# tester-7410.net
KiCad netlist of a schematic drawn in EAGLE
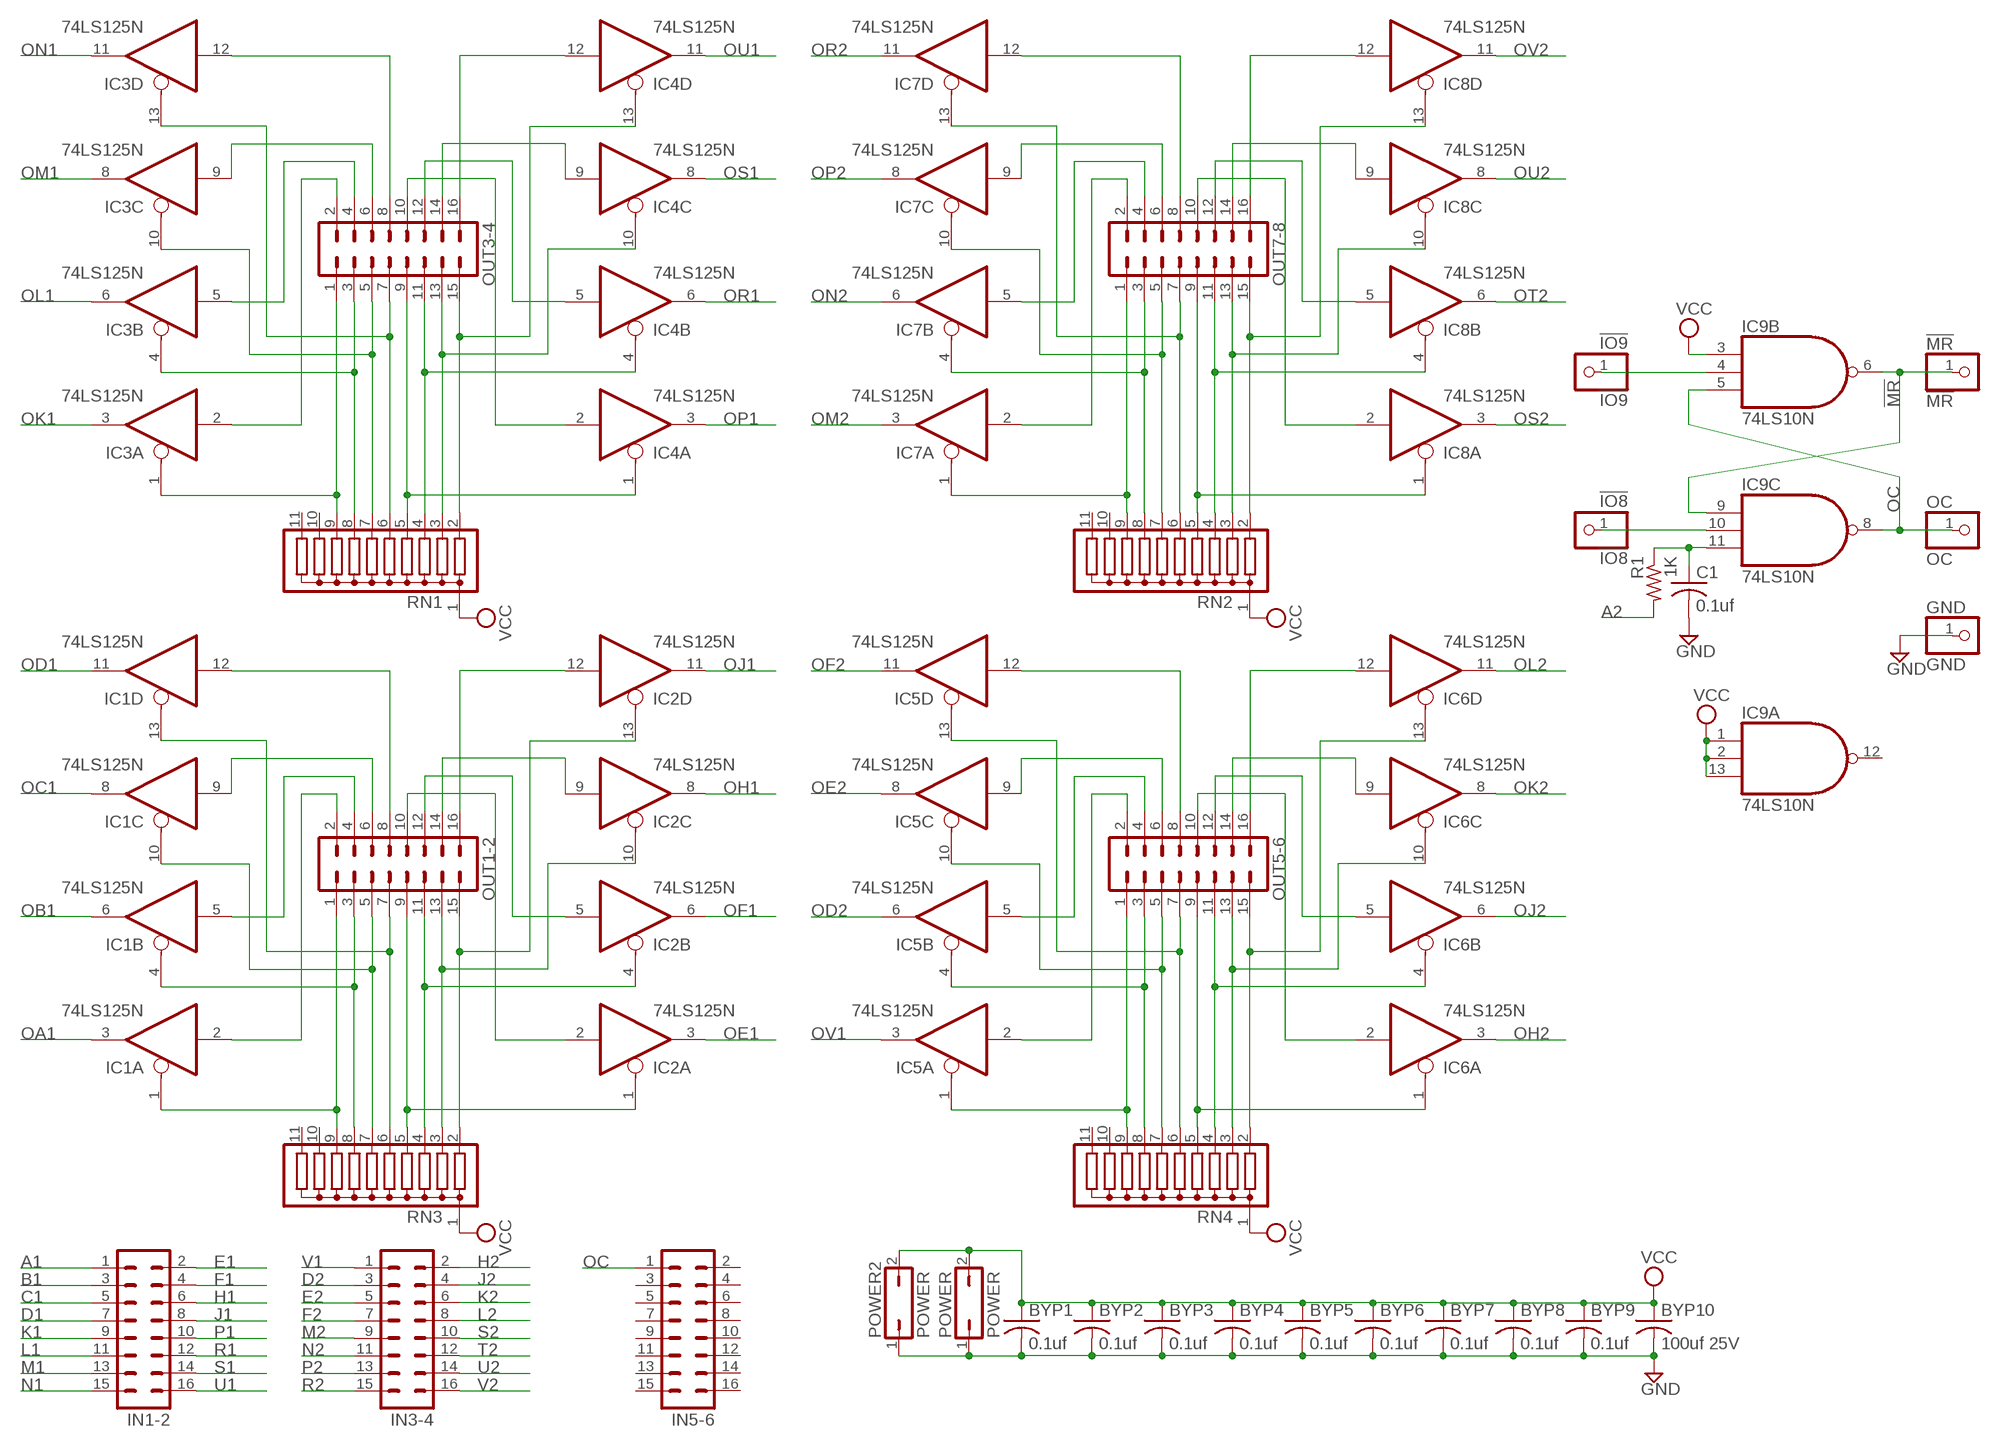
[diagram p0: schematic, sheet 1]
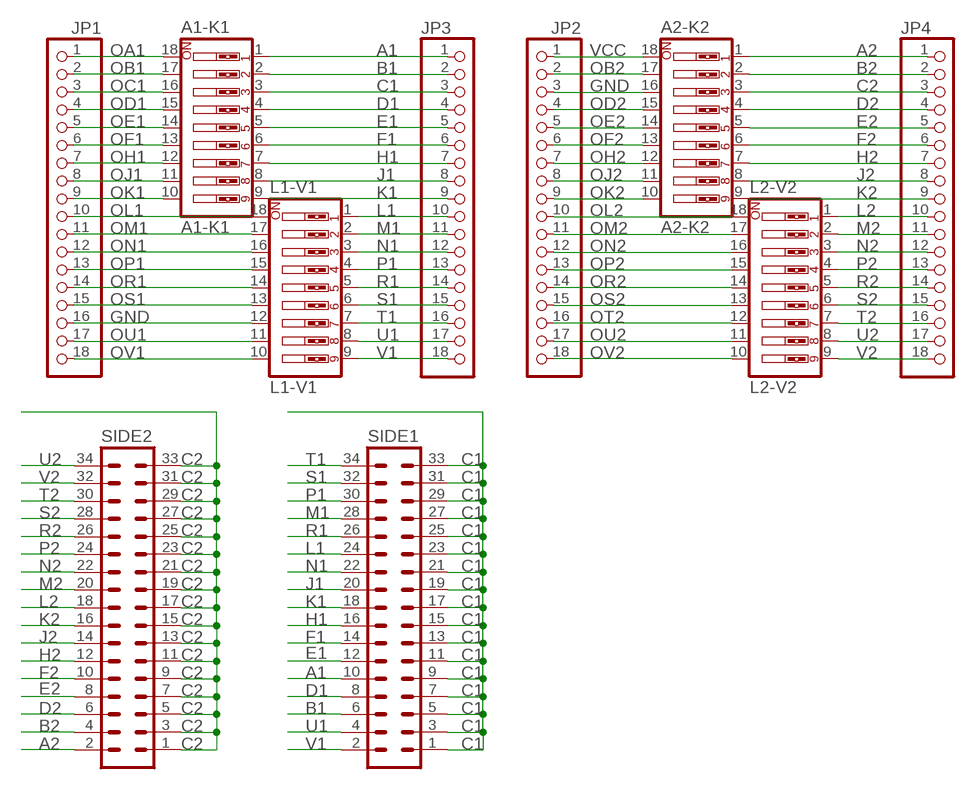
[diagram p1: schematic, sheet 2]

(export (version "E")
  (design (tool "Eeschema 10.0.6"))
  (components
    (comp (ref "!IO8")
      (value "!IO8")
      (footprint "eagle-import:1X01")
      (libsource (lib "eagle-import") (part "PINHD-1X1"))
    )
    (comp (ref "!IO9")
      (value "!IO9")
      (footprint "eagle-import:1X01")
      (libsource (lib "eagle-import") (part "PINHD-1X1"))
    )
    (comp (ref "!MR")
      (value "!MR")
      (footprint "eagle-import:1X01")
      (libsource (lib "eagle-import") (part "PINHD-1X1"))
    )
    (comp (ref "BYP1")
      (value "0.1uf")
      (footprint "eagle-import:C050-025X075")
      (libsource (lib "eagle-import") (part "C-US050-025X075"))
    )
    (comp (ref "BYP2")
      (value "0.1uf")
      (footprint "eagle-import:C050-025X075")
      (libsource (lib "eagle-import") (part "C-US050-025X075"))
    )
    (comp (ref "BYP3")
      (value "0.1uf")
      (footprint "eagle-import:C050-025X075")
      (libsource (lib "eagle-import") (part "C-US050-025X075"))
    )
    (comp (ref "BYP4")
      (value "0.1uf")
      (footprint "eagle-import:C050-025X075")
      (libsource (lib "eagle-import") (part "C-US050-025X075"))
    )
    (comp (ref "BYP5")
      (value "0.1uf")
      (footprint "eagle-import:C050-025X075")
      (libsource (lib "eagle-import") (part "C-US050-025X075"))
    )
    (comp (ref "BYP6")
      (value "0.1uf")
      (footprint "eagle-import:C050-025X075")
      (libsource (lib "eagle-import") (part "C-US050-025X075"))
    )
    (comp (ref "BYP7")
      (value "0.1uf")
      (footprint "eagle-import:C050-025X075")
      (libsource (lib "eagle-import") (part "C-US050-025X075"))
    )
    (comp (ref "BYP8")
      (value "0.1uf")
      (footprint "eagle-import:C050-025X075")
      (libsource (lib "eagle-import") (part "C-US050-025X075"))
    )
    (comp (ref "BYP9")
      (value "0.1uf")
      (footprint "eagle-import:C050-025X075")
      (libsource (lib "eagle-import") (part "C-US050-025X075"))
    )
    (comp (ref "BYP10")
      (value "100uf 25V")
      (footprint "eagle-import:C150-064X183")
      (libsource (lib "eagle-import") (part "C-US150-064X183"))
    )
    (comp (ref "C1")
      (value "0.1uf")
      (footprint "eagle-import:C050-025X075")
      (libsource (lib "eagle-import") (part "C-US050-025X075"))
    )
    (comp (ref "GND")
      (value "GND")
      (footprint "eagle-import:1X01")
      (libsource (lib "eagle-import") (part "PINHD-1X1"))
    )
    (comp (ref "IC1")
      (value "74LS125N")
      (footprint "eagle-import:DIL14")
      (libsource (lib "eagle-import") (part "74125NLS"))
    )
    (comp (ref "IC2")
      (value "74LS125N")
      (footprint "eagle-import:DIL14")
      (libsource (lib "eagle-import") (part "74125NLS"))
    )
    (comp (ref "IC3")
      (value "74LS125N")
      (footprint "eagle-import:DIL14")
      (libsource (lib "eagle-import") (part "74125NLS"))
    )
    (comp (ref "IC4")
      (value "74LS125N")
      (footprint "eagle-import:DIL14")
      (libsource (lib "eagle-import") (part "74125NLS"))
    )
    (comp (ref "IC5")
      (value "74LS125N")
      (footprint "eagle-import:DIL14")
      (libsource (lib "eagle-import") (part "74125NLS"))
    )
    (comp (ref "IC6")
      (value "74LS125N")
      (footprint "eagle-import:DIL14")
      (libsource (lib "eagle-import") (part "74125NLS"))
    )
    (comp (ref "IC7")
      (value "74LS125N")
      (footprint "eagle-import:DIL14")
      (libsource (lib "eagle-import") (part "74125NLS"))
    )
    (comp (ref "IC8")
      (value "74LS125N")
      (footprint "eagle-import:DIL14")
      (libsource (lib "eagle-import") (part "74125NLS"))
    )
    (comp (ref "IC9")
      (value "74LS10N")
      (footprint "eagle-import:DIL14")
      (libsource (lib "eagle-import") (part "7410NLS"))
    )
    (comp (ref "IN1-2")
      (value "MA08-2")
      (footprint "eagle-import:MA08-2")
      (libsource (lib "eagle-import") (part "MA08-2"))
    )
    (comp (ref "IN3-4")
      (value "MA08-2")
      (footprint "eagle-import:MA08-2")
      (libsource (lib "eagle-import") (part "MA08-2"))
    )
    (comp (ref "IN5-6")
      (value "MA08-2")
      (footprint "eagle-import:MA08-2")
      (libsource (lib "eagle-import") (part "MA08-2"))
    )
    (comp (ref "OC")
      (value "OC")
      (footprint "eagle-import:1X01")
      (libsource (lib "eagle-import") (part "PINHD-1X1"))
    )
    (comp (ref "OUT1-2")
      (value "MA08-2")
      (footprint "eagle-import:MA08-2")
      (libsource (lib "eagle-import") (part "MA08-2"))
    )
    (comp (ref "OUT3-4")
      (value "MA08-2")
      (footprint "eagle-import:MA08-2")
      (libsource (lib "eagle-import") (part "MA08-2"))
    )
    (comp (ref "OUT5-6")
      (value "MA08-2")
      (footprint "eagle-import:MA08-2")
      (libsource (lib "eagle-import") (part "MA08-2"))
    )
    (comp (ref "OUT7-8")
      (value "MA08-2")
      (footprint "eagle-import:MA08-2")
      (libsource (lib "eagle-import") (part "MA08-2"))
    )
    (comp (ref "POWER")
      (value "POWER")
      (footprint "eagle-import:JP1")
      (libsource (lib "eagle-import") (part "JP1Q"))
    )
    (comp (ref "POWER2")
      (value "POWER")
      (footprint "eagle-import:JP1")
      (libsource (lib "eagle-import") (part "JP1Q"))
    )
    (comp (ref "R1")
      (value "1K")
      (footprint "eagle-import:0207_10")
      (libsource (lib "eagle-import") (part "R-US_0207/10"))
    )
    (comp (ref "RN1")
      (value "G10R")
      (footprint "eagle-import:SIL11")
      (libsource (lib "eagle-import") (part "G10R"))
    )
    (comp (ref "RN2")
      (value "G10R")
      (footprint "eagle-import:SIL11")
      (libsource (lib "eagle-import") (part "G10R"))
    )
    (comp (ref "RN3")
      (value "G10R")
      (footprint "eagle-import:SIL11")
      (libsource (lib "eagle-import") (part "G10R"))
    )
    (comp (ref "RN4")
      (value "G10R")
      (footprint "eagle-import:SIL11")
      (libsource (lib "eagle-import") (part "G10R"))
    )
    (comp (ref "A1-K1")
      (value "A1-K1")
      (footprint "eagle-import:EDG-09")
      (libsource (lib "eagle-import") (part "SW_DIP-9"))
    )
    (comp (ref "A2-K2")
      (value "A2-K2")
      (footprint "eagle-import:EDG-09")
      (libsource (lib "eagle-import") (part "SW_DIP-9"))
    )
    (comp (ref "JP1")
      (value "PINHD-1X18")
      (footprint "eagle-import:1X18")
      (libsource (lib "eagle-import") (part "PINHD-1X18"))
    )
    (comp (ref "JP2")
      (value "PINHD-1X18")
      (footprint "eagle-import:1X18")
      (libsource (lib "eagle-import") (part "PINHD-1X18"))
    )
    (comp (ref "JP3")
      (value "PINHD-1X18")
      (footprint "eagle-import:1X18")
      (libsource (lib "eagle-import") (part "PINHD-1X18"))
    )
    (comp (ref "JP4")
      (value "PINHD-1X18")
      (footprint "eagle-import:1X18")
      (libsource (lib "eagle-import") (part "PINHD-1X18"))
    )
    (comp (ref "L1-V1")
      (value "L1-V1")
      (footprint "eagle-import:EDG-09")
      (libsource (lib "eagle-import") (part "SW_DIP-9"))
    )
    (comp (ref "L2-V2")
      (value "L2-V2")
      (footprint "eagle-import:EDG-09")
      (libsource (lib "eagle-import") (part "SW_DIP-9"))
    )
    (comp (ref "SIDE1")
      (value "MA17-2")
      (footprint "eagle-import:MA17-2")
      (libsource (lib "eagle-import") (part "MA17-2"))
    )
    (comp (ref "SIDE2")
      (value "MA17-2")
      (footprint "eagle-import:MA17-2")
      (libsource (lib "eagle-import") (part "MA17-2"))
    )
  )
  (nets
    (net (code "1") (name "A1") (class "Default")
      (node (ref "A1-K1") (pin "1") (pinfunction "1_1") (pintype "passive"))
      (node (ref "IN1-2") (pin "1") (pinfunction "1_1") (pintype "passive"))
      (node (ref "JP3") (pin "1") (pinfunction "1_1") (pintype "passive"))
      (node (ref "SIDE1") (pin "10") (pinfunction "10_10") (pintype "passive"))
    )
    (net (code "2") (name "A2") (class "Default")
      (node (ref "A2-K2") (pin "1") (pinfunction "1_1") (pintype "passive"))
      (node (ref "JP4") (pin "1") (pinfunction "1_1") (pintype "passive"))
      (node (ref "R1") (pin "2") (pinfunction "2_2") (pintype "passive"))
      (node (ref "SIDE2") (pin "2") (pinfunction "2_2") (pintype "passive"))
    )
    (net (code "3") (name "B1") (class "Default")
      (node (ref "A1-K1") (pin "2") (pinfunction "2_2") (pintype "passive"))
      (node (ref "IN1-2") (pin "3") (pinfunction "3_3") (pintype "passive"))
      (node (ref "JP3") (pin "2") (pinfunction "2_2") (pintype "passive"))
      (node (ref "SIDE1") (pin "6") (pinfunction "6_6") (pintype "passive"))
    )
    (net (code "4") (name "B2") (class "Default")
      (node (ref "A2-K2") (pin "2") (pinfunction "2_2") (pintype "passive"))
      (node (ref "JP4") (pin "2") (pinfunction "2_2") (pintype "passive"))
      (node (ref "SIDE2") (pin "4") (pinfunction "4_4") (pintype "passive"))
    )
    (net (code "5") (name "C1") (class "Default")
      (node (ref "A1-K1") (pin "3") (pinfunction "3_3") (pintype "passive"))
      (node (ref "IN1-2") (pin "5") (pinfunction "5_5") (pintype "passive"))
      (node (ref "JP3") (pin "3") (pinfunction "3_3") (pintype "passive"))
      (node (ref "SIDE1") (pin "1") (pinfunction "1_1") (pintype "passive"))
      (node (ref "SIDE1") (pin "11") (pinfunction "11_11") (pintype "passive"))
      (node (ref "SIDE1") (pin "13") (pinfunction "13_13") (pintype "passive"))
      (node (ref "SIDE1") (pin "15") (pinfunction "15_15") (pintype "passive"))
      (node (ref "SIDE1") (pin "17") (pinfunction "17_17") (pintype "passive"))
      (node (ref "SIDE1") (pin "19") (pinfunction "19_19") (pintype "passive"))
      (node (ref "SIDE1") (pin "21") (pinfunction "21_21") (pintype "passive"))
      (node (ref "SIDE1") (pin "23") (pinfunction "23_23") (pintype "passive"))
      (node (ref "SIDE1") (pin "25") (pinfunction "25_25") (pintype "passive"))
      (node (ref "SIDE1") (pin "27") (pinfunction "27_27") (pintype "passive"))
      (node (ref "SIDE1") (pin "29") (pinfunction "29_29") (pintype "passive"))
      (node (ref "SIDE1") (pin "3") (pinfunction "3_3") (pintype "passive"))
      (node (ref "SIDE1") (pin "31") (pinfunction "31_31") (pintype "passive"))
      (node (ref "SIDE1") (pin "33") (pinfunction "33_33") (pintype "passive"))
      (node (ref "SIDE1") (pin "5") (pinfunction "5_5") (pintype "passive"))
      (node (ref "SIDE1") (pin "7") (pinfunction "7_7") (pintype "passive"))
      (node (ref "SIDE1") (pin "9") (pinfunction "9_9") (pintype "passive"))
    )
    (net (code "6") (name "C2") (class "Default")
      (node (ref "A2-K2") (pin "3") (pinfunction "3_3") (pintype "passive"))
      (node (ref "JP4") (pin "3") (pinfunction "3_3") (pintype "passive"))
      (node (ref "SIDE2") (pin "1") (pinfunction "1_1") (pintype "passive"))
      (node (ref "SIDE2") (pin "11") (pinfunction "11_11") (pintype "passive"))
      (node (ref "SIDE2") (pin "13") (pinfunction "13_13") (pintype "passive"))
      (node (ref "SIDE2") (pin "15") (pinfunction "15_15") (pintype "passive"))
      (node (ref "SIDE2") (pin "17") (pinfunction "17_17") (pintype "passive"))
      (node (ref "SIDE2") (pin "19") (pinfunction "19_19") (pintype "passive"))
      (node (ref "SIDE2") (pin "21") (pinfunction "21_21") (pintype "passive"))
      (node (ref "SIDE2") (pin "23") (pinfunction "23_23") (pintype "passive"))
      (node (ref "SIDE2") (pin "25") (pinfunction "25_25") (pintype "passive"))
      (node (ref "SIDE2") (pin "27") (pinfunction "27_27") (pintype "passive"))
      (node (ref "SIDE2") (pin "29") (pinfunction "29_29") (pintype "passive"))
      (node (ref "SIDE2") (pin "3") (pinfunction "3_3") (pintype "passive"))
      (node (ref "SIDE2") (pin "31") (pinfunction "31_31") (pintype "passive"))
      (node (ref "SIDE2") (pin "33") (pinfunction "33_33") (pintype "passive"))
      (node (ref "SIDE2") (pin "5") (pinfunction "5_5") (pintype "passive"))
      (node (ref "SIDE2") (pin "7") (pinfunction "7_7") (pintype "passive"))
      (node (ref "SIDE2") (pin "9") (pinfunction "9_9") (pintype "passive"))
    )
    (net (code "7") (name "D1") (class "Default")
      (node (ref "A1-K1") (pin "4") (pinfunction "4_4") (pintype "passive"))
      (node (ref "IN1-2") (pin "7") (pinfunction "7_7") (pintype "passive"))
      (node (ref "JP3") (pin "4") (pinfunction "4_4") (pintype "passive"))
      (node (ref "SIDE1") (pin "8") (pinfunction "8_8") (pintype "passive"))
    )
    (net (code "8") (name "D2") (class "Default")
      (node (ref "A2-K2") (pin "4") (pinfunction "4_4") (pintype "passive"))
      (node (ref "IN3-4") (pin "3") (pinfunction "3_3") (pintype "passive"))
      (node (ref "JP4") (pin "4") (pinfunction "4_4") (pintype "passive"))
      (node (ref "SIDE2") (pin "6") (pinfunction "6_6") (pintype "passive"))
    )
    (net (code "9") (name "E1") (class "Default")
      (node (ref "A1-K1") (pin "5") (pinfunction "5_5") (pintype "passive"))
      (node (ref "IN1-2") (pin "2") (pinfunction "2_2") (pintype "passive"))
      (node (ref "JP3") (pin "5") (pinfunction "5_5") (pintype "passive"))
      (node (ref "SIDE1") (pin "12") (pinfunction "12_12") (pintype "passive"))
    )
    (net (code "10") (name "E2") (class "Default")
      (node (ref "A2-K2") (pin "5") (pinfunction "5_5") (pintype "passive"))
      (node (ref "IN3-4") (pin "5") (pinfunction "5_5") (pintype "passive"))
      (node (ref "JP4") (pin "5") (pinfunction "5_5") (pintype "passive"))
      (node (ref "SIDE2") (pin "8") (pinfunction "8_8") (pintype "passive"))
    )
    (net (code "11") (name "F1") (class "Default")
      (node (ref "A1-K1") (pin "6") (pinfunction "6_6") (pintype "passive"))
      (node (ref "IN1-2") (pin "4") (pinfunction "4_4") (pintype "passive"))
      (node (ref "JP3") (pin "6") (pinfunction "6_6") (pintype "passive"))
      (node (ref "SIDE1") (pin "14") (pinfunction "14_14") (pintype "passive"))
    )
    (net (code "12") (name "F2") (class "Default")
      (node (ref "A2-K2") (pin "6") (pinfunction "6_6") (pintype "passive"))
      (node (ref "IN3-4") (pin "7") (pinfunction "7_7") (pintype "passive"))
      (node (ref "JP4") (pin "6") (pinfunction "6_6") (pintype "passive"))
      (node (ref "SIDE2") (pin "10") (pinfunction "10_10") (pintype "passive"))
    )
    (net (code "13") (name "GND") (class "Default")
      (node (ref "A2-K2") (pin "16") (pinfunction "16_16") (pintype "passive"))
      (node (ref "BYP1") (pin "2") (pinfunction "2_2") (pintype "passive"))
      (node (ref "BYP10") (pin "2") (pinfunction "2_2") (pintype "passive"))
      (node (ref "BYP2") (pin "2") (pinfunction "2_2") (pintype "passive"))
      (node (ref "BYP3") (pin "2") (pinfunction "2_2") (pintype "passive"))
      (node (ref "BYP4") (pin "2") (pinfunction "2_2") (pintype "passive"))
      (node (ref "BYP5") (pin "2") (pinfunction "2_2") (pintype "passive"))
      (node (ref "BYP6") (pin "2") (pinfunction "2_2") (pintype "passive"))
      (node (ref "BYP7") (pin "2") (pinfunction "2_2") (pintype "passive"))
      (node (ref "BYP8") (pin "2") (pinfunction "2_2") (pintype "passive"))
      (node (ref "BYP9") (pin "2") (pinfunction "2_2") (pintype "passive"))
      (node (ref "C1") (pin "2") (pinfunction "2_2") (pintype "passive"))
      (node (ref "GND") (pin "1") (pinfunction "1_1") (pintype "passive"))
      (node (ref "JP1") (pin "16") (pinfunction "16_16") (pintype "passive"))
      (node (ref "JP2") (pin "3") (pinfunction "3_3") (pintype "passive"))
      (node (ref "L1-V1") (pin "12") (pinfunction "12_12") (pintype "passive"))
      (node (ref "POWER") (pin "1") (pinfunction "1_1") (pintype "passive"))
      (node (ref "POWER2") (pin "1") (pinfunction "1_1") (pintype "passive"))
    )
    (net (code "14") (name "H1") (class "Default")
      (node (ref "A1-K1") (pin "7") (pinfunction "7_7") (pintype "passive"))
      (node (ref "IN1-2") (pin "6") (pinfunction "6_6") (pintype "passive"))
      (node (ref "JP3") (pin "7") (pinfunction "7_7") (pintype "passive"))
      (node (ref "SIDE1") (pin "16") (pinfunction "16_16") (pintype "passive"))
    )
    (net (code "15") (name "H2") (class "Default")
      (node (ref "A2-K2") (pin "7") (pinfunction "7_7") (pintype "passive"))
      (node (ref "IN3-4") (pin "2") (pinfunction "2_2") (pintype "passive"))
      (node (ref "JP4") (pin "7") (pinfunction "7_7") (pintype "passive"))
      (node (ref "SIDE2") (pin "12") (pinfunction "12_12") (pintype "passive"))
    )
    (net (code "16") (name "J1") (class "Default")
      (node (ref "A1-K1") (pin "8") (pinfunction "8_8") (pintype "passive"))
      (node (ref "IN1-2") (pin "8") (pinfunction "8_8") (pintype "passive"))
      (node (ref "JP3") (pin "8") (pinfunction "8_8") (pintype "passive"))
      (node (ref "SIDE1") (pin "20") (pinfunction "20_20") (pintype "passive"))
    )
    (net (code "17") (name "J2") (class "Default")
      (node (ref "A2-K2") (pin "8") (pinfunction "8_8") (pintype "passive"))
      (node (ref "IN3-4") (pin "4") (pinfunction "4_4") (pintype "passive"))
      (node (ref "JP4") (pin "8") (pinfunction "8_8") (pintype "passive"))
      (node (ref "SIDE2") (pin "14") (pinfunction "14_14") (pintype "passive"))
    )
    (net (code "18") (name "K1") (class "Default")
      (node (ref "A1-K1") (pin "9") (pinfunction "9_9") (pintype "passive"))
      (node (ref "IN1-2") (pin "9") (pinfunction "9_9") (pintype "passive"))
      (node (ref "JP3") (pin "9") (pinfunction "9_9") (pintype "passive"))
      (node (ref "SIDE1") (pin "18") (pinfunction "18_18") (pintype "passive"))
    )
    (net (code "19") (name "K2") (class "Default")
      (node (ref "A2-K2") (pin "9") (pinfunction "9_9") (pintype "passive"))
      (node (ref "IN3-4") (pin "6") (pinfunction "6_6") (pintype "passive"))
      (node (ref "JP4") (pin "9") (pinfunction "9_9") (pintype "passive"))
      (node (ref "SIDE2") (pin "16") (pinfunction "16_16") (pintype "passive"))
    )
    (net (code "20") (name "L1") (class "Default")
      (node (ref "IN1-2") (pin "11") (pinfunction "11_11") (pintype "passive"))
      (node (ref "JP3") (pin "10") (pinfunction "10_10") (pintype "passive"))
      (node (ref "L1-V1") (pin "1") (pinfunction "1_1") (pintype "passive"))
      (node (ref "SIDE1") (pin "24") (pinfunction "24_24") (pintype "passive"))
    )
    (net (code "21") (name "L2") (class "Default")
      (node (ref "IN3-4") (pin "8") (pinfunction "8_8") (pintype "passive"))
      (node (ref "JP4") (pin "10") (pinfunction "10_10") (pintype "passive"))
      (node (ref "L2-V2") (pin "1") (pinfunction "1_1") (pintype "passive"))
      (node (ref "SIDE2") (pin "18") (pinfunction "18_18") (pintype "passive"))
    )
    (net (code "22") (name "M1") (class "Default")
      (node (ref "IN1-2") (pin "13") (pinfunction "13_13") (pintype "passive"))
      (node (ref "JP3") (pin "11") (pinfunction "11_11") (pintype "passive"))
      (node (ref "L1-V1") (pin "2") (pinfunction "2_2") (pintype "passive"))
      (node (ref "SIDE1") (pin "28") (pinfunction "28_28") (pintype "passive"))
    )
    (net (code "23") (name "M2") (class "Default")
      (node (ref "IN3-4") (pin "9") (pinfunction "9_9") (pintype "passive"))
      (node (ref "JP4") (pin "11") (pinfunction "11_11") (pintype "passive"))
      (node (ref "L2-V2") (pin "2") (pinfunction "2_2") (pintype "passive"))
      (node (ref "SIDE2") (pin "20") (pinfunction "20_20") (pintype "passive"))
    )
    (net (code "24") (name "N1") (class "Default")
      (node (ref "IN1-2") (pin "15") (pinfunction "15_15") (pintype "passive"))
      (node (ref "JP3") (pin "12") (pinfunction "12_12") (pintype "passive"))
      (node (ref "L1-V1") (pin "3") (pinfunction "3_3") (pintype "passive"))
      (node (ref "SIDE1") (pin "22") (pinfunction "22_22") (pintype "passive"))
    )
    (net (code "25") (name "N2") (class "Default")
      (node (ref "IN3-4") (pin "11") (pinfunction "11_11") (pintype "passive"))
      (node (ref "JP4") (pin "12") (pinfunction "12_12") (pintype "passive"))
      (node (ref "L2-V2") (pin "3") (pinfunction "3_3") (pintype "passive"))
      (node (ref "SIDE2") (pin "22") (pinfunction "22_22") (pintype "passive"))
    )
    (net (code "26") (name "Net-(IC1A-I)") (class "Default")
      (node (ref "IC1") (pin "2") (pinfunction "I_2") (pintype "input"))
      (node (ref "OUT1-2") (pin "2") (pinfunction "2_2") (pintype "passive"))
    )
    (net (code "27") (name "Net-(IC1A-OE)") (class "Default")
      (node (ref "IC1") (pin "1") (pinfunction "OE_1") (pintype "input"))
      (node (ref "OUT1-2") (pin "1") (pinfunction "1_1") (pintype "passive"))
      (node (ref "RN3") (pin "9") (pinfunction "9_9") (pintype "passive"))
    )
    (net (code "28") (name "Net-(IC1B-I)") (class "Default")
      (node (ref "IC1") (pin "5") (pinfunction "I_5") (pintype "input"))
      (node (ref "OUT1-2") (pin "4") (pinfunction "4_4") (pintype "passive"))
    )
    (net (code "29") (name "Net-(IC1B-OE)") (class "Default")
      (node (ref "IC1") (pin "4") (pinfunction "OE_4") (pintype "input"))
      (node (ref "OUT1-2") (pin "3") (pinfunction "3_3") (pintype "passive"))
      (node (ref "RN3") (pin "8") (pinfunction "8_8") (pintype "passive"))
    )
    (net (code "30") (name "Net-(IC1C-I)") (class "Default")
      (node (ref "IC1") (pin "9") (pinfunction "I_9") (pintype "input"))
      (node (ref "OUT1-2") (pin "6") (pinfunction "6_6") (pintype "passive"))
    )
    (net (code "31") (name "Net-(IC1C-OE)") (class "Default")
      (node (ref "IC1") (pin "10") (pinfunction "OE_10") (pintype "input"))
      (node (ref "OUT1-2") (pin "5") (pinfunction "5_5") (pintype "passive"))
      (node (ref "RN3") (pin "7") (pinfunction "7_7") (pintype "passive"))
    )
    (net (code "32") (name "Net-(IC1D-I)") (class "Default")
      (node (ref "IC1") (pin "12") (pinfunction "I_12") (pintype "input"))
      (node (ref "OUT1-2") (pin "8") (pinfunction "8_8") (pintype "passive"))
    )
    (net (code "33") (name "Net-(IC1D-OE)") (class "Default")
      (node (ref "IC1") (pin "13") (pinfunction "OE_13") (pintype "input"))
      (node (ref "OUT1-2") (pin "7") (pinfunction "7_7") (pintype "passive"))
      (node (ref "RN3") (pin "6") (pinfunction "6_6") (pintype "passive"))
    )
    (net (code "34") (name "Net-(IC2A-I)") (class "Default")
      (node (ref "IC2") (pin "2") (pinfunction "I_2") (pintype "input"))
      (node (ref "OUT1-2") (pin "10") (pinfunction "10_10") (pintype "passive"))
    )
    (net (code "35") (name "Net-(IC2A-OE)") (class "Default")
      (node (ref "IC2") (pin "1") (pinfunction "OE_1") (pintype "input"))
      (node (ref "OUT1-2") (pin "9") (pinfunction "9_9") (pintype "passive"))
      (node (ref "RN3") (pin "5") (pinfunction "5_5") (pintype "passive"))
    )
    (net (code "36") (name "Net-(IC2B-I)") (class "Default")
      (node (ref "IC2") (pin "5") (pinfunction "I_5") (pintype "input"))
      (node (ref "OUT1-2") (pin "12") (pinfunction "12_12") (pintype "passive"))
    )
    (net (code "37") (name "Net-(IC2B-OE)") (class "Default")
      (node (ref "IC2") (pin "4") (pinfunction "OE_4") (pintype "input"))
      (node (ref "OUT1-2") (pin "11") (pinfunction "11_11") (pintype "passive"))
      (node (ref "RN3") (pin "4") (pinfunction "4_4") (pintype "passive"))
    )
    (net (code "38") (name "Net-(IC2C-I)") (class "Default")
      (node (ref "IC2") (pin "9") (pinfunction "I_9") (pintype "input"))
      (node (ref "OUT1-2") (pin "14") (pinfunction "14_14") (pintype "passive"))
    )
    (net (code "39") (name "Net-(IC2C-OE)") (class "Default")
      (node (ref "IC2") (pin "10") (pinfunction "OE_10") (pintype "input"))
      (node (ref "OUT1-2") (pin "13") (pinfunction "13_13") (pintype "passive"))
      (node (ref "RN3") (pin "3") (pinfunction "3_3") (pintype "passive"))
    )
    (net (code "40") (name "Net-(IC2D-I)") (class "Default")
      (node (ref "IC2") (pin "12") (pinfunction "I_12") (pintype "input"))
      (node (ref "OUT1-2") (pin "16") (pinfunction "16_16") (pintype "passive"))
    )
    (net (code "41") (name "Net-(IC2D-OE)") (class "Default")
      (node (ref "IC2") (pin "13") (pinfunction "OE_13") (pintype "input"))
      (node (ref "OUT1-2") (pin "15") (pinfunction "15_15") (pintype "passive"))
      (node (ref "RN3") (pin "2") (pinfunction "2_2") (pintype "passive"))
    )
    (net (code "42") (name "Net-(IC3A-I)") (class "Default")
      (node (ref "IC3") (pin "2") (pinfunction "I_2") (pintype "input"))
      (node (ref "OUT3-4") (pin "2") (pinfunction "2_2") (pintype "passive"))
    )
    (net (code "43") (name "Net-(IC3A-OE)") (class "Default")
      (node (ref "IC3") (pin "1") (pinfunction "OE_1") (pintype "input"))
      (node (ref "OUT3-4") (pin "1") (pinfunction "1_1") (pintype "passive"))
      (node (ref "RN1") (pin "9") (pinfunction "9_9") (pintype "passive"))
    )
    (net (code "44") (name "Net-(IC3B-I)") (class "Default")
      (node (ref "IC3") (pin "5") (pinfunction "I_5") (pintype "input"))
      (node (ref "OUT3-4") (pin "4") (pinfunction "4_4") (pintype "passive"))
    )
    (net (code "45") (name "Net-(IC3B-OE)") (class "Default")
      (node (ref "IC3") (pin "4") (pinfunction "OE_4") (pintype "input"))
      (node (ref "OUT3-4") (pin "3") (pinfunction "3_3") (pintype "passive"))
      (node (ref "RN1") (pin "8") (pinfunction "8_8") (pintype "passive"))
    )
    (net (code "46") (name "Net-(IC3C-I)") (class "Default")
      (node (ref "IC3") (pin "9") (pinfunction "I_9") (pintype "input"))
      (node (ref "OUT3-4") (pin "6") (pinfunction "6_6") (pintype "passive"))
    )
    (net (code "47") (name "Net-(IC3C-OE)") (class "Default")
      (node (ref "IC3") (pin "10") (pinfunction "OE_10") (pintype "input"))
      (node (ref "OUT3-4") (pin "5") (pinfunction "5_5") (pintype "passive"))
      (node (ref "RN1") (pin "7") (pinfunction "7_7") (pintype "passive"))
    )
    (net (code "48") (name "Net-(IC3D-I)") (class "Default")
      (node (ref "IC3") (pin "12") (pinfunction "I_12") (pintype "input"))
      (node (ref "OUT3-4") (pin "8") (pinfunction "8_8") (pintype "passive"))
    )
    (net (code "49") (name "Net-(IC3D-OE)") (class "Default")
      (node (ref "IC3") (pin "13") (pinfunction "OE_13") (pintype "input"))
      (node (ref "OUT3-4") (pin "7") (pinfunction "7_7") (pintype "passive"))
      (node (ref "RN1") (pin "6") (pinfunction "6_6") (pintype "passive"))
    )
    (net (code "50") (name "Net-(IC4A-I)") (class "Default")
      (node (ref "IC4") (pin "2") (pinfunction "I_2") (pintype "input"))
      (node (ref "OUT3-4") (pin "10") (pinfunction "10_10") (pintype "passive"))
    )
    (net (code "51") (name "Net-(IC4A-OE)") (class "Default")
      (node (ref "IC4") (pin "1") (pinfunction "OE_1") (pintype "input"))
      (node (ref "OUT3-4") (pin "9") (pinfunction "9_9") (pintype "passive"))
      (node (ref "RN1") (pin "5") (pinfunction "5_5") (pintype "passive"))
    )
    (net (code "52") (name "Net-(IC4B-I)") (class "Default")
      (node (ref "IC4") (pin "5") (pinfunction "I_5") (pintype "input"))
      (node (ref "OUT3-4") (pin "12") (pinfunction "12_12") (pintype "passive"))
    )
    (net (code "53") (name "Net-(IC4B-OE)") (class "Default")
      (node (ref "IC4") (pin "4") (pinfunction "OE_4") (pintype "input"))
      (node (ref "OUT3-4") (pin "11") (pinfunction "11_11") (pintype "passive"))
      (node (ref "RN1") (pin "4") (pinfunction "4_4") (pintype "passive"))
    )
    (net (code "54") (name "Net-(IC4C-I)") (class "Default")
      (node (ref "IC4") (pin "9") (pinfunction "I_9") (pintype "input"))
      (node (ref "OUT3-4") (pin "14") (pinfunction "14_14") (pintype "passive"))
    )
    (net (code "55") (name "Net-(IC4C-OE)") (class "Default")
      (node (ref "IC4") (pin "10") (pinfunction "OE_10") (pintype "input"))
      (node (ref "OUT3-4") (pin "13") (pinfunction "13_13") (pintype "passive"))
      (node (ref "RN1") (pin "3") (pinfunction "3_3") (pintype "passive"))
    )
    (net (code "56") (name "Net-(IC4D-I)") (class "Default")
      (node (ref "IC4") (pin "12") (pinfunction "I_12") (pintype "input"))
      (node (ref "OUT3-4") (pin "16") (pinfunction "16_16") (pintype "passive"))
    )
    (net (code "57") (name "Net-(IC4D-OE)") (class "Default")
      (node (ref "IC4") (pin "13") (pinfunction "OE_13") (pintype "input"))
      (node (ref "OUT3-4") (pin "15") (pinfunction "15_15") (pintype "passive"))
      (node (ref "RN1") (pin "2") (pinfunction "2_2") (pintype "passive"))
    )
    (net (code "58") (name "Net-(IC5A-I)") (class "Default")
      (node (ref "IC5") (pin "2") (pinfunction "I_2") (pintype "input"))
      (node (ref "OUT5-6") (pin "2") (pinfunction "2_2") (pintype "passive"))
    )
    (net (code "59") (name "Net-(IC5A-OE)") (class "Default")
      (node (ref "IC5") (pin "1") (pinfunction "OE_1") (pintype "input"))
      (node (ref "OUT5-6") (pin "1") (pinfunction "1_1") (pintype "passive"))
      (node (ref "RN4") (pin "9") (pinfunction "9_9") (pintype "passive"))
    )
    (net (code "60") (name "Net-(IC5B-I)") (class "Default")
      (node (ref "IC5") (pin "5") (pinfunction "I_5") (pintype "input"))
      (node (ref "OUT5-6") (pin "4") (pinfunction "4_4") (pintype "passive"))
    )
    (net (code "61") (name "Net-(IC5B-OE)") (class "Default")
      (node (ref "IC5") (pin "4") (pinfunction "OE_4") (pintype "input"))
      (node (ref "OUT5-6") (pin "3") (pinfunction "3_3") (pintype "passive"))
      (node (ref "RN4") (pin "8") (pinfunction "8_8") (pintype "passive"))
    )
    (net (code "62") (name "Net-(IC5C-I)") (class "Default")
      (node (ref "IC5") (pin "9") (pinfunction "I_9") (pintype "input"))
      (node (ref "OUT5-6") (pin "6") (pinfunction "6_6") (pintype "passive"))
    )
    (net (code "63") (name "Net-(IC5C-OE)") (class "Default")
      (node (ref "IC5") (pin "10") (pinfunction "OE_10") (pintype "input"))
      (node (ref "OUT5-6") (pin "5") (pinfunction "5_5") (pintype "passive"))
      (node (ref "RN4") (pin "7") (pinfunction "7_7") (pintype "passive"))
    )
    (net (code "64") (name "Net-(IC5D-I)") (class "Default")
      (node (ref "IC5") (pin "12") (pinfunction "I_12") (pintype "input"))
      (node (ref "OUT5-6") (pin "8") (pinfunction "8_8") (pintype "passive"))
    )
    (net (code "65") (name "Net-(IC5D-OE)") (class "Default")
      (node (ref "IC5") (pin "13") (pinfunction "OE_13") (pintype "input"))
      (node (ref "OUT5-6") (pin "7") (pinfunction "7_7") (pintype "passive"))
      (node (ref "RN4") (pin "6") (pinfunction "6_6") (pintype "passive"))
    )
    (net (code "66") (name "Net-(IC6A-I)") (class "Default")
      (node (ref "IC6") (pin "2") (pinfunction "I_2") (pintype "input"))
      (node (ref "OUT5-6") (pin "10") (pinfunction "10_10") (pintype "passive"))
    )
    (net (code "67") (name "Net-(IC6A-OE)") (class "Default")
      (node (ref "IC6") (pin "1") (pinfunction "OE_1") (pintype "input"))
      (node (ref "OUT5-6") (pin "9") (pinfunction "9_9") (pintype "passive"))
      (node (ref "RN4") (pin "5") (pinfunction "5_5") (pintype "passive"))
    )
    (net (code "68") (name "Net-(IC6B-I)") (class "Default")
      (node (ref "IC6") (pin "5") (pinfunction "I_5") (pintype "input"))
      (node (ref "OUT5-6") (pin "12") (pinfunction "12_12") (pintype "passive"))
    )
    (net (code "69") (name "Net-(IC6B-OE)") (class "Default")
      (node (ref "IC6") (pin "4") (pinfunction "OE_4") (pintype "input"))
      (node (ref "OUT5-6") (pin "11") (pinfunction "11_11") (pintype "passive"))
      (node (ref "RN4") (pin "4") (pinfunction "4_4") (pintype "passive"))
    )
    (net (code "70") (name "Net-(IC6C-I)") (class "Default")
      (node (ref "IC6") (pin "9") (pinfunction "I_9") (pintype "input"))
      (node (ref "OUT5-6") (pin "14") (pinfunction "14_14") (pintype "passive"))
    )
    (net (code "71") (name "Net-(IC6C-OE)") (class "Default")
      (node (ref "IC6") (pin "10") (pinfunction "OE_10") (pintype "input"))
      (node (ref "OUT5-6") (pin "13") (pinfunction "13_13") (pintype "passive"))
      (node (ref "RN4") (pin "3") (pinfunction "3_3") (pintype "passive"))
    )
    (net (code "72") (name "Net-(IC6D-I)") (class "Default")
      (node (ref "IC6") (pin "12") (pinfunction "I_12") (pintype "input"))
      (node (ref "OUT5-6") (pin "16") (pinfunction "16_16") (pintype "passive"))
    )
    (net (code "73") (name "Net-(IC6D-OE)") (class "Default")
      (node (ref "IC6") (pin "13") (pinfunction "OE_13") (pintype "input"))
      (node (ref "OUT5-6") (pin "15") (pinfunction "15_15") (pintype "passive"))
      (node (ref "RN4") (pin "2") (pinfunction "2_2") (pintype "passive"))
    )
    (net (code "74") (name "Net-(IC7A-I)") (class "Default")
      (node (ref "IC7") (pin "2") (pinfunction "I_2") (pintype "input"))
      (node (ref "OUT7-8") (pin "2") (pinfunction "2_2") (pintype "passive"))
    )
    (net (code "75") (name "Net-(IC7A-OE)") (class "Default")
      (node (ref "IC7") (pin "1") (pinfunction "OE_1") (pintype "input"))
      (node (ref "OUT7-8") (pin "1") (pinfunction "1_1") (pintype "passive"))
      (node (ref "RN2") (pin "9") (pinfunction "9_9") (pintype "passive"))
    )
    (net (code "76") (name "Net-(IC7B-I)") (class "Default")
      (node (ref "IC7") (pin "5") (pinfunction "I_5") (pintype "input"))
      (node (ref "OUT7-8") (pin "4") (pinfunction "4_4") (pintype "passive"))
    )
    (net (code "77") (name "Net-(IC7B-OE)") (class "Default")
      (node (ref "IC7") (pin "4") (pinfunction "OE_4") (pintype "input"))
      (node (ref "OUT7-8") (pin "3") (pinfunction "3_3") (pintype "passive"))
      (node (ref "RN2") (pin "8") (pinfunction "8_8") (pintype "passive"))
    )
    (net (code "78") (name "Net-(IC7C-I)") (class "Default")
      (node (ref "IC7") (pin "9") (pinfunction "I_9") (pintype "input"))
      (node (ref "OUT7-8") (pin "6") (pinfunction "6_6") (pintype "passive"))
    )
    (net (code "79") (name "Net-(IC7C-OE)") (class "Default")
      (node (ref "IC7") (pin "10") (pinfunction "OE_10") (pintype "input"))
      (node (ref "OUT7-8") (pin "5") (pinfunction "5_5") (pintype "passive"))
      (node (ref "RN2") (pin "7") (pinfunction "7_7") (pintype "passive"))
    )
    (net (code "80") (name "Net-(IC7D-I)") (class "Default")
      (node (ref "IC7") (pin "12") (pinfunction "I_12") (pintype "input"))
      (node (ref "OUT7-8") (pin "8") (pinfunction "8_8") (pintype "passive"))
    )
    (net (code "81") (name "Net-(IC7D-OE)") (class "Default")
      (node (ref "IC7") (pin "13") (pinfunction "OE_13") (pintype "input"))
      (node (ref "OUT7-8") (pin "7") (pinfunction "7_7") (pintype "passive"))
      (node (ref "RN2") (pin "6") (pinfunction "6_6") (pintype "passive"))
    )
    (net (code "82") (name "Net-(IC8A-I)") (class "Default")
      (node (ref "IC8") (pin "2") (pinfunction "I_2") (pintype "input"))
      (node (ref "OUT7-8") (pin "10") (pinfunction "10_10") (pintype "passive"))
    )
    (net (code "83") (name "Net-(IC8A-OE)") (class "Default")
      (node (ref "IC8") (pin "1") (pinfunction "OE_1") (pintype "input"))
      (node (ref "OUT7-8") (pin "9") (pinfunction "9_9") (pintype "passive"))
      (node (ref "RN2") (pin "5") (pinfunction "5_5") (pintype "passive"))
    )
    (net (code "84") (name "Net-(IC8B-I)") (class "Default")
      (node (ref "IC8") (pin "5") (pinfunction "I_5") (pintype "input"))
      (node (ref "OUT7-8") (pin "12") (pinfunction "12_12") (pintype "passive"))
    )
    (net (code "85") (name "Net-(IC8B-OE)") (class "Default")
      (node (ref "IC8") (pin "4") (pinfunction "OE_4") (pintype "input"))
      (node (ref "OUT7-8") (pin "11") (pinfunction "11_11") (pintype "passive"))
      (node (ref "RN2") (pin "4") (pinfunction "4_4") (pintype "passive"))
    )
    (net (code "86") (name "Net-(IC8C-I)") (class "Default")
      (node (ref "IC8") (pin "9") (pinfunction "I_9") (pintype "input"))
      (node (ref "OUT7-8") (pin "14") (pinfunction "14_14") (pintype "passive"))
    )
    (net (code "87") (name "Net-(IC8C-OE)") (class "Default")
      (node (ref "IC8") (pin "10") (pinfunction "OE_10") (pintype "input"))
      (node (ref "OUT7-8") (pin "13") (pinfunction "13_13") (pintype "passive"))
      (node (ref "RN2") (pin "3") (pinfunction "3_3") (pintype "passive"))
    )
    (net (code "88") (name "Net-(IC8D-I)") (class "Default")
      (node (ref "IC8") (pin "12") (pinfunction "I_12") (pintype "input"))
      (node (ref "OUT7-8") (pin "16") (pinfunction "16_16") (pintype "passive"))
    )
    (net (code "89") (name "Net-(IC8D-OE)") (class "Default")
      (node (ref "IC8") (pin "13") (pinfunction "OE_13") (pintype "input"))
      (node (ref "OUT7-8") (pin "15") (pinfunction "15_15") (pintype "passive"))
      (node (ref "RN2") (pin "2") (pinfunction "2_2") (pintype "passive"))
    )
    (net (code "90") (name "Net-(IC9B-I1)") (class "Default")
      (node (ref "!IO9") (pin "1") (pinfunction "1_1") (pintype "passive"))
      (node (ref "IC9") (pin "4") (pinfunction "I1_4") (pintype "input"))
    )
    (net (code "91") (name "Net-(IC9C-I1)") (class "Default")
      (node (ref "!IO8") (pin "1") (pinfunction "1_1") (pintype "passive"))
      (node (ref "IC9") (pin "10") (pinfunction "I1_10") (pintype "input"))
    )
    (net (code "92") (name "Net-(IC9C-I2)") (class "Default")
      (node (ref "C1") (pin "1") (pinfunction "1_1") (pintype "passive"))
      (node (ref "IC9") (pin "11") (pinfunction "I2_11") (pintype "input"))
      (node (ref "R1") (pin "1") (pinfunction "1_1") (pintype "passive"))
    )
    (net (code "93") (name "OA1") (class "Default")
      (node (ref "A1-K1") (pin "18") (pinfunction "18_18") (pintype "passive"))
      (node (ref "IC1") (pin "3") (pinfunction "O_3") (pintype "tri_state"))
      (node (ref "JP1") (pin "1") (pinfunction "1_1") (pintype "passive"))
    )
    (net (code "94") (name "OB1") (class "Default")
      (node (ref "A1-K1") (pin "17") (pinfunction "17_17") (pintype "passive"))
      (node (ref "IC1") (pin "6") (pinfunction "O_6") (pintype "tri_state"))
      (node (ref "JP1") (pin "2") (pinfunction "2_2") (pintype "passive"))
    )
    (net (code "95") (name "OB2") (class "Default")
      (node (ref "A2-K2") (pin "17") (pinfunction "17_17") (pintype "passive"))
      (node (ref "JP2") (pin "2") (pinfunction "2_2") (pintype "passive"))
    )
    (net (code "96") (name "OC") (class "Default")
      (node (ref "IC9") (pin "5") (pinfunction "I2_5") (pintype "input"))
      (node (ref "IC9") (pin "8") (pinfunction "O_8") (pintype "output"))
      (node (ref "IN5-6") (pin "1") (pinfunction "1_1") (pintype "passive"))
      (node (ref "OC") (pin "1") (pinfunction "1_1") (pintype "passive"))
    )
    (net (code "97") (name "OC1") (class "Default")
      (node (ref "A1-K1") (pin "16") (pinfunction "16_16") (pintype "passive"))
      (node (ref "IC1") (pin "8") (pinfunction "O_8") (pintype "tri_state"))
      (node (ref "JP1") (pin "3") (pinfunction "3_3") (pintype "passive"))
    )
    (net (code "98") (name "OD1") (class "Default")
      (node (ref "A1-K1") (pin "15") (pinfunction "15_15") (pintype "passive"))
      (node (ref "IC1") (pin "11") (pinfunction "O_11") (pintype "tri_state"))
      (node (ref "JP1") (pin "4") (pinfunction "4_4") (pintype "passive"))
    )
    (net (code "99") (name "OD2") (class "Default")
      (node (ref "A2-K2") (pin "15") (pinfunction "15_15") (pintype "passive"))
      (node (ref "IC5") (pin "6") (pinfunction "O_6") (pintype "tri_state"))
      (node (ref "JP2") (pin "4") (pinfunction "4_4") (pintype "passive"))
    )
    (net (code "100") (name "OE1") (class "Default")
      (node (ref "A1-K1") (pin "14") (pinfunction "14_14") (pintype "passive"))
      (node (ref "IC2") (pin "3") (pinfunction "O_3") (pintype "tri_state"))
      (node (ref "JP1") (pin "5") (pinfunction "5_5") (pintype "passive"))
    )
    (net (code "101") (name "OE2") (class "Default")
      (node (ref "A2-K2") (pin "14") (pinfunction "14_14") (pintype "passive"))
      (node (ref "IC5") (pin "8") (pinfunction "O_8") (pintype "tri_state"))
      (node (ref "JP2") (pin "5") (pinfunction "5_5") (pintype "passive"))
    )
    (net (code "102") (name "OF1") (class "Default")
      (node (ref "A1-K1") (pin "13") (pinfunction "13_13") (pintype "passive"))
      (node (ref "IC2") (pin "6") (pinfunction "O_6") (pintype "tri_state"))
      (node (ref "JP1") (pin "6") (pinfunction "6_6") (pintype "passive"))
    )
    (net (code "103") (name "OF2") (class "Default")
      (node (ref "A2-K2") (pin "13") (pinfunction "13_13") (pintype "passive"))
      (node (ref "IC5") (pin "11") (pinfunction "O_11") (pintype "tri_state"))
      (node (ref "JP2") (pin "6") (pinfunction "6_6") (pintype "passive"))
    )
    (net (code "104") (name "OH1") (class "Default")
      (node (ref "A1-K1") (pin "12") (pinfunction "12_12") (pintype "passive"))
      (node (ref "IC2") (pin "8") (pinfunction "O_8") (pintype "tri_state"))
      (node (ref "JP1") (pin "7") (pinfunction "7_7") (pintype "passive"))
    )
    (net (code "105") (name "OH2") (class "Default")
      (node (ref "A2-K2") (pin "12") (pinfunction "12_12") (pintype "passive"))
      (node (ref "IC6") (pin "3") (pinfunction "O_3") (pintype "tri_state"))
      (node (ref "JP2") (pin "7") (pinfunction "7_7") (pintype "passive"))
    )
    (net (code "106") (name "OJ1") (class "Default")
      (node (ref "A1-K1") (pin "11") (pinfunction "11_11") (pintype "passive"))
      (node (ref "IC2") (pin "11") (pinfunction "O_11") (pintype "tri_state"))
      (node (ref "JP1") (pin "8") (pinfunction "8_8") (pintype "passive"))
    )
    (net (code "107") (name "OJ2") (class "Default")
      (node (ref "A2-K2") (pin "11") (pinfunction "11_11") (pintype "passive"))
      (node (ref "IC6") (pin "6") (pinfunction "O_6") (pintype "tri_state"))
      (node (ref "JP2") (pin "8") (pinfunction "8_8") (pintype "passive"))
    )
    (net (code "108") (name "OK1") (class "Default")
      (node (ref "A1-K1") (pin "10") (pinfunction "10_10") (pintype "passive"))
      (node (ref "IC3") (pin "3") (pinfunction "O_3") (pintype "tri_state"))
      (node (ref "JP1") (pin "9") (pinfunction "9_9") (pintype "passive"))
    )
    (net (code "109") (name "OK2") (class "Default")
      (node (ref "A2-K2") (pin "10") (pinfunction "10_10") (pintype "passive"))
      (node (ref "IC6") (pin "8") (pinfunction "O_8") (pintype "tri_state"))
      (node (ref "JP2") (pin "9") (pinfunction "9_9") (pintype "passive"))
    )
    (net (code "110") (name "OL1") (class "Default")
      (node (ref "IC3") (pin "6") (pinfunction "O_6") (pintype "tri_state"))
      (node (ref "JP1") (pin "10") (pinfunction "10_10") (pintype "passive"))
      (node (ref "L1-V1") (pin "18") (pinfunction "18_18") (pintype "passive"))
    )
    (net (code "111") (name "OL2") (class "Default")
      (node (ref "IC6") (pin "11") (pinfunction "O_11") (pintype "tri_state"))
      (node (ref "JP2") (pin "10") (pinfunction "10_10") (pintype "passive"))
      (node (ref "L2-V2") (pin "18") (pinfunction "18_18") (pintype "passive"))
    )
    (net (code "112") (name "OM1") (class "Default")
      (node (ref "IC3") (pin "8") (pinfunction "O_8") (pintype "tri_state"))
      (node (ref "JP1") (pin "11") (pinfunction "11_11") (pintype "passive"))
      (node (ref "L1-V1") (pin "17") (pinfunction "17_17") (pintype "passive"))
    )
    (net (code "113") (name "OM2") (class "Default")
      (node (ref "IC7") (pin "3") (pinfunction "O_3") (pintype "tri_state"))
      (node (ref "JP2") (pin "11") (pinfunction "11_11") (pintype "passive"))
      (node (ref "L2-V2") (pin "17") (pinfunction "17_17") (pintype "passive"))
    )
    (net (code "114") (name "ON1") (class "Default")
      (node (ref "IC3") (pin "11") (pinfunction "O_11") (pintype "tri_state"))
      (node (ref "JP1") (pin "12") (pinfunction "12_12") (pintype "passive"))
      (node (ref "L1-V1") (pin "16") (pinfunction "16_16") (pintype "passive"))
    )
    (net (code "115") (name "ON2") (class "Default")
      (node (ref "IC7") (pin "6") (pinfunction "O_6") (pintype "tri_state"))
      (node (ref "JP2") (pin "12") (pinfunction "12_12") (pintype "passive"))
      (node (ref "L2-V2") (pin "16") (pinfunction "16_16") (pintype "passive"))
    )
    (net (code "116") (name "OP1") (class "Default")
      (node (ref "IC4") (pin "3") (pinfunction "O_3") (pintype "tri_state"))
      (node (ref "JP1") (pin "13") (pinfunction "13_13") (pintype "passive"))
      (node (ref "L1-V1") (pin "15") (pinfunction "15_15") (pintype "passive"))
    )
    (net (code "117") (name "OP2") (class "Default")
      (node (ref "IC7") (pin "8") (pinfunction "O_8") (pintype "tri_state"))
      (node (ref "JP2") (pin "13") (pinfunction "13_13") (pintype "passive"))
      (node (ref "L2-V2") (pin "15") (pinfunction "15_15") (pintype "passive"))
    )
    (net (code "118") (name "OR1") (class "Default")
      (node (ref "IC4") (pin "6") (pinfunction "O_6") (pintype "tri_state"))
      (node (ref "JP1") (pin "14") (pinfunction "14_14") (pintype "passive"))
      (node (ref "L1-V1") (pin "14") (pinfunction "14_14") (pintype "passive"))
    )
    (net (code "119") (name "OR2") (class "Default")
      (node (ref "IC7") (pin "11") (pinfunction "O_11") (pintype "tri_state"))
      (node (ref "JP2") (pin "14") (pinfunction "14_14") (pintype "passive"))
      (node (ref "L2-V2") (pin "14") (pinfunction "14_14") (pintype "passive"))
    )
    (net (code "120") (name "OS1") (class "Default")
      (node (ref "IC4") (pin "8") (pinfunction "O_8") (pintype "tri_state"))
      (node (ref "JP1") (pin "15") (pinfunction "15_15") (pintype "passive"))
      (node (ref "L1-V1") (pin "13") (pinfunction "13_13") (pintype "passive"))
    )
    (net (code "121") (name "OS2") (class "Default")
      (node (ref "IC8") (pin "3") (pinfunction "O_3") (pintype "tri_state"))
      (node (ref "JP2") (pin "15") (pinfunction "15_15") (pintype "passive"))
      (node (ref "L2-V2") (pin "13") (pinfunction "13_13") (pintype "passive"))
    )
    (net (code "122") (name "OT2") (class "Default")
      (node (ref "IC8") (pin "6") (pinfunction "O_6") (pintype "tri_state"))
      (node (ref "JP2") (pin "16") (pinfunction "16_16") (pintype "passive"))
      (node (ref "L2-V2") (pin "12") (pinfunction "12_12") (pintype "passive"))
    )
    (net (code "123") (name "OU1") (class "Default")
      (node (ref "IC4") (pin "11") (pinfunction "O_11") (pintype "tri_state"))
      (node (ref "JP1") (pin "17") (pinfunction "17_17") (pintype "passive"))
      (node (ref "L1-V1") (pin "11") (pinfunction "11_11") (pintype "passive"))
    )
    (net (code "124") (name "OU2") (class "Default")
      (node (ref "IC8") (pin "8") (pinfunction "O_8") (pintype "tri_state"))
      (node (ref "JP2") (pin "17") (pinfunction "17_17") (pintype "passive"))
      (node (ref "L2-V2") (pin "11") (pinfunction "11_11") (pintype "passive"))
    )
    (net (code "125") (name "OV1") (class "Default")
      (node (ref "IC5") (pin "3") (pinfunction "O_3") (pintype "tri_state"))
      (node (ref "JP1") (pin "18") (pinfunction "18_18") (pintype "passive"))
      (node (ref "L1-V1") (pin "10") (pinfunction "10_10") (pintype "passive"))
    )
    (net (code "126") (name "OV2") (class "Default")
      (node (ref "IC8") (pin "11") (pinfunction "O_11") (pintype "tri_state"))
      (node (ref "JP2") (pin "18") (pinfunction "18_18") (pintype "passive"))
      (node (ref "L2-V2") (pin "10") (pinfunction "10_10") (pintype "passive"))
    )
    (net (code "127") (name "P1") (class "Default")
      (node (ref "IN1-2") (pin "10") (pinfunction "10_10") (pintype "passive"))
      (node (ref "JP3") (pin "13") (pinfunction "13_13") (pintype "passive"))
      (node (ref "L1-V1") (pin "4") (pinfunction "4_4") (pintype "passive"))
      (node (ref "SIDE1") (pin "30") (pinfunction "30_30") (pintype "passive"))
    )
    (net (code "128") (name "P2") (class "Default")
      (node (ref "IN3-4") (pin "13") (pinfunction "13_13") (pintype "passive"))
      (node (ref "JP4") (pin "13") (pinfunction "13_13") (pintype "passive"))
      (node (ref "L2-V2") (pin "4") (pinfunction "4_4") (pintype "passive"))
      (node (ref "SIDE2") (pin "24") (pinfunction "24_24") (pintype "passive"))
    )
    (net (code "129") (name "R1") (class "Default")
      (node (ref "IN1-2") (pin "12") (pinfunction "12_12") (pintype "passive"))
      (node (ref "JP3") (pin "14") (pinfunction "14_14") (pintype "passive"))
      (node (ref "L1-V1") (pin "5") (pinfunction "5_5") (pintype "passive"))
      (node (ref "SIDE1") (pin "26") (pinfunction "26_26") (pintype "passive"))
    )
    (net (code "130") (name "R2") (class "Default")
      (node (ref "IN3-4") (pin "15") (pinfunction "15_15") (pintype "passive"))
      (node (ref "JP4") (pin "14") (pinfunction "14_14") (pintype "passive"))
      (node (ref "L2-V2") (pin "5") (pinfunction "5_5") (pintype "passive"))
      (node (ref "SIDE2") (pin "26") (pinfunction "26_26") (pintype "passive"))
    )
    (net (code "131") (name "S1") (class "Default")
      (node (ref "IN1-2") (pin "14") (pinfunction "14_14") (pintype "passive"))
      (node (ref "JP3") (pin "15") (pinfunction "15_15") (pintype "passive"))
      (node (ref "L1-V1") (pin "6") (pinfunction "6_6") (pintype "passive"))
      (node (ref "SIDE1") (pin "32") (pinfunction "32_32") (pintype "passive"))
    )
    (net (code "132") (name "S2") (class "Default")
      (node (ref "IN3-4") (pin "10") (pinfunction "10_10") (pintype "passive"))
      (node (ref "JP4") (pin "15") (pinfunction "15_15") (pintype "passive"))
      (node (ref "L2-V2") (pin "6") (pinfunction "6_6") (pintype "passive"))
      (node (ref "SIDE2") (pin "28") (pinfunction "28_28") (pintype "passive"))
    )
    (net (code "133") (name "T1") (class "Default")
      (node (ref "JP3") (pin "16") (pinfunction "16_16") (pintype "passive"))
      (node (ref "L1-V1") (pin "7") (pinfunction "7_7") (pintype "passive"))
      (node (ref "SIDE1") (pin "34") (pinfunction "34_34") (pintype "passive"))
    )
    (net (code "134") (name "T2") (class "Default")
      (node (ref "IN3-4") (pin "12") (pinfunction "12_12") (pintype "passive"))
      (node (ref "JP4") (pin "16") (pinfunction "16_16") (pintype "passive"))
      (node (ref "L2-V2") (pin "7") (pinfunction "7_7") (pintype "passive"))
      (node (ref "SIDE2") (pin "30") (pinfunction "30_30") (pintype "passive"))
    )
    (net (code "135") (name "U1") (class "Default")
      (node (ref "IN1-2") (pin "16") (pinfunction "16_16") (pintype "passive"))
      (node (ref "JP3") (pin "17") (pinfunction "17_17") (pintype "passive"))
      (node (ref "L1-V1") (pin "8") (pinfunction "8_8") (pintype "passive"))
      (node (ref "SIDE1") (pin "4") (pinfunction "4_4") (pintype "passive"))
    )
    (net (code "136") (name "U2") (class "Default")
      (node (ref "IN3-4") (pin "14") (pinfunction "14_14") (pintype "passive"))
      (node (ref "JP4") (pin "17") (pinfunction "17_17") (pintype "passive"))
      (node (ref "L2-V2") (pin "8") (pinfunction "8_8") (pintype "passive"))
      (node (ref "SIDE2") (pin "34") (pinfunction "34_34") (pintype "passive"))
    )
    (net (code "137") (name "V1") (class "Default")
      (node (ref "IN3-4") (pin "1") (pinfunction "1_1") (pintype "passive"))
      (node (ref "JP3") (pin "18") (pinfunction "18_18") (pintype "passive"))
      (node (ref "L1-V1") (pin "9") (pinfunction "9_9") (pintype "passive"))
      (node (ref "SIDE1") (pin "2") (pinfunction "2_2") (pintype "passive"))
    )
    (net (code "138") (name "V2") (class "Default")
      (node (ref "IN3-4") (pin "16") (pinfunction "16_16") (pintype "passive"))
      (node (ref "JP4") (pin "18") (pinfunction "18_18") (pintype "passive"))
      (node (ref "L2-V2") (pin "9") (pinfunction "9_9") (pintype "passive"))
      (node (ref "SIDE2") (pin "32") (pinfunction "32_32") (pintype "passive"))
    )
    (net (code "139") (name "VCC") (class "Default")
      (node (ref "A2-K2") (pin "18") (pinfunction "18_18") (pintype "passive"))
      (node (ref "BYP1") (pin "1") (pinfunction "1_1") (pintype "passive"))
      (node (ref "BYP10") (pin "1") (pinfunction "1_1") (pintype "passive"))
      (node (ref "BYP2") (pin "1") (pinfunction "1_1") (pintype "passive"))
      (node (ref "BYP3") (pin "1") (pinfunction "1_1") (pintype "passive"))
      (node (ref "BYP4") (pin "1") (pinfunction "1_1") (pintype "passive"))
      (node (ref "BYP5") (pin "1") (pinfunction "1_1") (pintype "passive"))
      (node (ref "BYP6") (pin "1") (pinfunction "1_1") (pintype "passive"))
      (node (ref "BYP7") (pin "1") (pinfunction "1_1") (pintype "passive"))
      (node (ref "BYP8") (pin "1") (pinfunction "1_1") (pintype "passive"))
      (node (ref "BYP9") (pin "1") (pinfunction "1_1") (pintype "passive"))
      (node (ref "IC9") (pin "1") (pinfunction "I0_1") (pintype "input"))
      (node (ref "IC9") (pin "13") (pinfunction "I2_13") (pintype "input"))
      (node (ref "IC9") (pin "2") (pinfunction "I1_2") (pintype "input"))
      (node (ref "IC9") (pin "3") (pinfunction "I0_3") (pintype "input"))
      (node (ref "JP2") (pin "1") (pinfunction "1_1") (pintype "passive"))
      (node (ref "POWER") (pin "2") (pinfunction "2_2") (pintype "passive"))
      (node (ref "POWER2") (pin "2") (pinfunction "2_2") (pintype "passive"))
      (node (ref "RN1") (pin "1") (pinfunction "1_1") (pintype "passive"))
      (node (ref "RN2") (pin "1") (pinfunction "1_1") (pintype "passive"))
      (node (ref "RN3") (pin "1") (pinfunction "1_1") (pintype "passive"))
      (node (ref "RN4") (pin "1") (pinfunction "1_1") (pintype "passive"))
    )
    (net (code "140") (name "unconnected-(IC9A-O-Pad12)") (class "Default")
      (node (ref "IC9") (pin "12") (pinfunction "O_12") (pintype "output"))
    )
    (net (code "141") (name "unconnected-(IN5-6-Pad2)") (class "Default")
      (node (ref "IN5-6") (pin "2") (pinfunction "2_2") (pintype "passive"))
    )
    (net (code "142") (name "unconnected-(IN5-6-Pad3)") (class "Default")
      (node (ref "IN5-6") (pin "3") (pinfunction "3_3") (pintype "passive"))
    )
    (net (code "143") (name "unconnected-(IN5-6-Pad4)") (class "Default")
      (node (ref "IN5-6") (pin "4") (pinfunction "4_4") (pintype "passive"))
    )
    (net (code "144") (name "unconnected-(IN5-6-Pad5)") (class "Default")
      (node (ref "IN5-6") (pin "5") (pinfunction "5_5") (pintype "passive"))
    )
    (net (code "145") (name "unconnected-(IN5-6-Pad6)") (class "Default")
      (node (ref "IN5-6") (pin "6") (pinfunction "6_6") (pintype "passive"))
    )
    (net (code "146") (name "unconnected-(IN5-6-Pad7)") (class "Default")
      (node (ref "IN5-6") (pin "7") (pinfunction "7_7") (pintype "passive"))
    )
    (net (code "147") (name "unconnected-(IN5-6-Pad8)") (class "Default")
      (node (ref "IN5-6") (pin "8") (pinfunction "8_8") (pintype "passive"))
    )
    (net (code "148") (name "unconnected-(IN5-6-Pad9)") (class "Default")
      (node (ref "IN5-6") (pin "9") (pinfunction "9_9") (pintype "passive"))
    )
    (net (code "149") (name "unconnected-(IN5-6-Pad10)") (class "Default")
      (node (ref "IN5-6") (pin "10") (pinfunction "10_10") (pintype "passive"))
    )
    (net (code "150") (name "unconnected-(IN5-6-Pad11)") (class "Default")
      (node (ref "IN5-6") (pin "11") (pinfunction "11_11") (pintype "passive"))
    )
    (net (code "151") (name "unconnected-(IN5-6-Pad12)") (class "Default")
      (node (ref "IN5-6") (pin "12") (pinfunction "12_12") (pintype "passive"))
    )
    (net (code "152") (name "unconnected-(IN5-6-Pad13)") (class "Default")
      (node (ref "IN5-6") (pin "13") (pinfunction "13_13") (pintype "passive"))
    )
    (net (code "153") (name "unconnected-(IN5-6-Pad14)") (class "Default")
      (node (ref "IN5-6") (pin "14") (pinfunction "14_14") (pintype "passive"))
    )
    (net (code "154") (name "unconnected-(IN5-6-Pad15)") (class "Default")
      (node (ref "IN5-6") (pin "15") (pinfunction "15_15") (pintype "passive"))
    )
    (net (code "155") (name "unconnected-(IN5-6-Pad16)") (class "Default")
      (node (ref "IN5-6") (pin "16") (pinfunction "16_16") (pintype "passive"))
    )
    (net (code "156") (name "unconnected-(RN1-Pad10)") (class "Default")
      (node (ref "RN1") (pin "10") (pinfunction "10_10") (pintype "passive"))
    )
    (net (code "157") (name "unconnected-(RN1-Pad11)") (class "Default")
      (node (ref "RN1") (pin "11") (pinfunction "11_11") (pintype "passive"))
    )
    (net (code "158") (name "unconnected-(RN2-Pad10)") (class "Default")
      (node (ref "RN2") (pin "10") (pinfunction "10_10") (pintype "passive"))
    )
    (net (code "159") (name "unconnected-(RN2-Pad11)") (class "Default")
      (node (ref "RN2") (pin "11") (pinfunction "11_11") (pintype "passive"))
    )
    (net (code "160") (name "unconnected-(RN3-Pad10)") (class "Default")
      (node (ref "RN3") (pin "10") (pinfunction "10_10") (pintype "passive"))
    )
    (net (code "161") (name "unconnected-(RN3-Pad11)") (class "Default")
      (node (ref "RN3") (pin "11") (pinfunction "11_11") (pintype "passive"))
    )
    (net (code "162") (name "unconnected-(RN4-Pad10)") (class "Default")
      (node (ref "RN4") (pin "10") (pinfunction "10_10") (pintype "passive"))
    )
    (net (code "163") (name "unconnected-(RN4-Pad11)") (class "Default")
      (node (ref "RN4") (pin "11") (pinfunction "11_11") (pintype "passive"))
    )
    (net (code "164") (name "~{MR}") (class "Default")
      (node (ref "!MR") (pin "1") (pinfunction "1_1") (pintype "passive"))
      (node (ref "IC9") (pin "6") (pinfunction "O_6") (pintype "output"))
      (node (ref "IC9") (pin "9") (pinfunction "I0_9") (pintype "input"))
    )
  )
)
